# CurrentSenseLowSide.net
KiCad netlist of a schematic drawn in Altium Designer
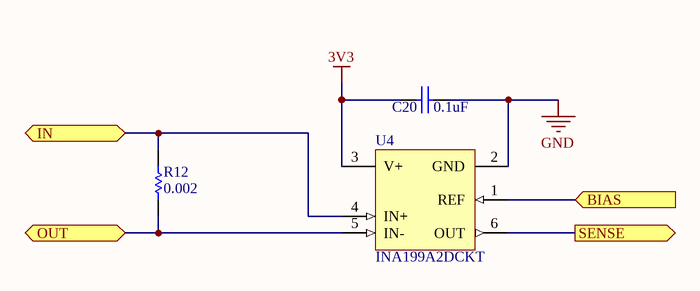
[diagram p0: CurrentSenseLowSide.SchDoc]

(export (version "E")
  (design (tool "Eeschema 10.0.6"))
  (components
    (comp (ref "C20")
      (value "0.1uF")
      (footprint "CAPC0603(1608)100_L")
      (description "CAP 100nF 100V ±10% 0603 (1608 Metric) Thickness 1mm SMD")
      (fields (field (name "TOLERANCE") "Â±10%"))
      (libsource (lib "Altium Content Vault") (part "CAP"))
    )
    (comp (ref "R12")
      (value "0.002")
      (footprint "0805-SHUNT")
      (libsource (lib "Components") (part "PMR10EZPFV2L00"))
    )
    (comp (ref "U4")
      (value "INA199A2DCKT")
      (footprint "DCK0006A_L")
      (libsource (lib "Altium Content Vault") (part "CMP-0704-00045-2"))
    )
  )
  (nets
    (net (code "1") (name "/BIAS") (class "Default")
      (node (ref "U4") (pin "1") (pinfunction "REF_1") (pintype "input"))
    )
    (net (code "2") (name "/IN") (class "Default")
      (node (ref "R12") (pin "2") (pinfunction "2_2") (pintype "passive"))
      (node (ref "U4") (pin "4") (pinfunction "IN+_4") (pintype "input"))
    )
    (net (code "3") (name "/OUT") (class "Default")
      (node (ref "R12") (pin "1") (pinfunction "1_1") (pintype "passive"))
      (node (ref "U4") (pin "5") (pinfunction "IN-_5") (pintype "input"))
    )
    (net (code "4") (name "/SENSE") (class "Default")
      (node (ref "U4") (pin "6") (pinfunction "OUT_6") (pintype "output"))
    )
    (net (code "5") (name "3V3") (class "Default")
      (node (ref "C20") (pin "1") (pinfunction "1_1") (pintype "passive"))
      (node (ref "U4") (pin "3") (pinfunction "V+_3") (pintype "power_in"))
    )
    (net (code "6") (name "GND") (class "Default")
      (node (ref "C20") (pin "2") (pinfunction "2_2") (pintype "passive"))
      (node (ref "U4") (pin "2") (pinfunction "GND_2") (pintype "power_in"))
    )
  )
)
